# bikelights.net
KiCad netlist of a schematic drawn in EAGLE
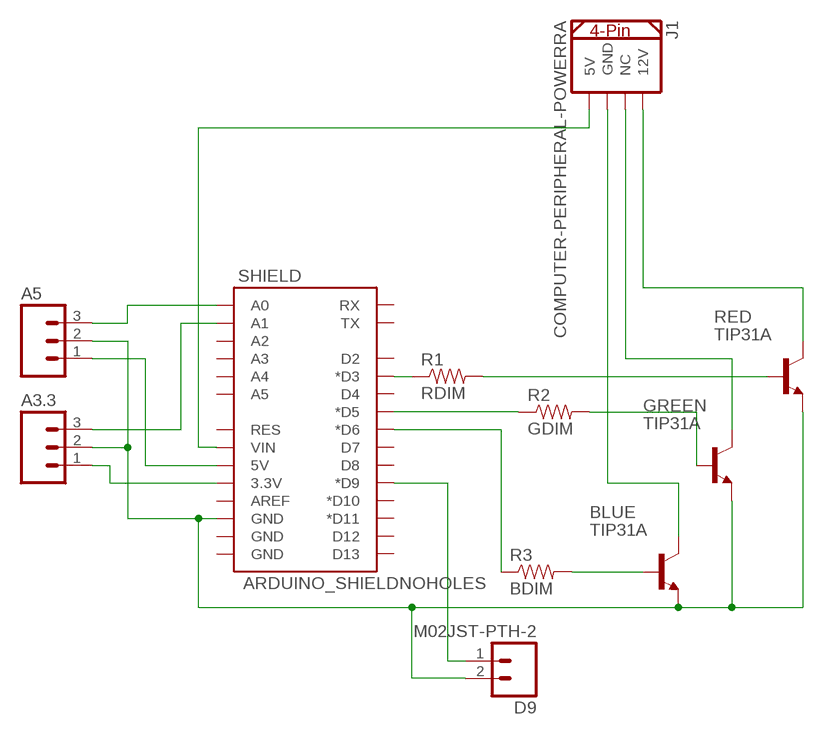
[diagram p0: schematic, sheet 1]

(export (version "E")
  (design (tool "Eeschema 10.0.6"))
  (components
    (comp (ref "A3.3")
      (value "M03JST-PTH")
      (footprint "eagle-import:JST-3-PTH")
      (libsource (lib "eagle-import") (part "M03JST-PTH"))
    )
    (comp (ref "A5")
      (value "M03JST-PTH")
      (footprint "eagle-import:JST-3-PTH")
      (libsource (lib "eagle-import") (part "M03JST-PTH"))
    )
    (comp (ref "BLUE")
      (value "TIP31A")
      (footprint "eagle-import:TO220")
      (libsource (lib "eagle-import") (part "TIP31A"))
    )
    (comp (ref "D9")
      (value "M02JST-PTH-2")
      (footprint "eagle-import:JST-2-PTH")
      (libsource (lib "eagle-import") (part "M02JST-PTH-2"))
    )
    (comp (ref "GREEN")
      (value "TIP31A")
      (footprint "eagle-import:TO220")
      (libsource (lib "eagle-import") (part "TIP31A"))
    )
    (comp (ref "J1")
      (value "COMPUTER-PERIPHERAL-POWERRA")
      (footprint "eagle-import:COMPUTER-PERIPHERAL-POWER-RA")
      (libsource (lib "eagle-import") (part "COMPUTER-PERIPHERAL-POWERRA"))
    )
    (comp (ref "R1")
      (value "RDIM")
      (footprint "eagle-import:AXIAL-0.3EZ")
      (libsource (lib "eagle-import") (part "RESISTOREZ"))
    )
    (comp (ref "R2")
      (value "GDIM")
      (footprint "eagle-import:AXIAL-0.3EZ")
      (libsource (lib "eagle-import") (part "RESISTOREZ"))
    )
    (comp (ref "R3")
      (value "BDIM")
      (footprint "eagle-import:AXIAL-0.3EZ")
      (libsource (lib "eagle-import") (part "RESISTOREZ"))
    )
    (comp (ref "RED")
      (value "TIP31A")
      (footprint "eagle-import:TO220")
      (libsource (lib "eagle-import") (part "TIP31A"))
    )
    (comp (ref "SHIELD")
      (value "ARDUINO_SHIELDNOHOLES")
      (footprint "eagle-import:DUEMILANOVE_SHIELD_NOHOLES")
      (libsource (lib "eagle-import") (part "ARDUINO_SHIELDNOHOLES"))
    )
  )
  (nets
    (net (code "1") (name "Net-(A3.3-Pad1)") (class "Default")
      (node (ref "A3.3") (pin "1") (pinfunction "1_1") (pintype "passive"))
      (node (ref "SHIELD") (pin "3.3V") (pinfunction "3.3V_3.3V") (pintype "bidirectional"))
    )
    (net (code "2") (name "Net-(A3.3-Pad3)") (class "Default")
      (node (ref "A3.3") (pin "3") (pinfunction "3_3") (pintype "passive"))
      (node (ref "SHIELD") (pin "A1") (pinfunction "A1_A1") (pintype "bidirectional"))
    )
    (net (code "3") (name "Net-(A5-Pad1)") (class "Default")
      (node (ref "A5") (pin "1") (pinfunction "1_1") (pintype "passive"))
      (node (ref "SHIELD") (pin "5V") (pinfunction "5V_5V") (pintype "bidirectional"))
    )
    (net (code "4") (name "Net-(A5-Pad3)") (class "Default")
      (node (ref "A5") (pin "3") (pinfunction "3_3") (pintype "passive"))
      (node (ref "SHIELD") (pin "A0") (pinfunction "A0_A0") (pintype "bidirectional"))
    )
    (net (code "5") (name "Net-(BLUE-B)") (class "Default")
      (node (ref "BLUE") (pin "1") (pinfunction "B_1") (pintype "passive"))
      (node (ref "R3") (pin "P$2") (pinfunction "2_P$2") (pintype "passive"))
    )
    (net (code "6") (name "Net-(BLUE-C)") (class "Default")
      (node (ref "BLUE") (pin "2") (pinfunction "C_2") (pintype "passive"))
      (node (ref "J1") (pin "GND") (pinfunction "GND_GND") (pintype "passive"))
    )
    (net (code "7") (name "Net-(BLUE-E)") (class "Default")
      (node (ref "A3.3") (pin "2") (pinfunction "2_2") (pintype "passive"))
      (node (ref "A5") (pin "2") (pinfunction "2_2") (pintype "passive"))
      (node (ref "BLUE") (pin "3") (pinfunction "E_3") (pintype "passive"))
      (node (ref "D9") (pin "2") (pinfunction "2_2") (pintype "passive"))
      (node (ref "GREEN") (pin "3") (pinfunction "E_3") (pintype "passive"))
      (node (ref "RED") (pin "3") (pinfunction "E_3") (pintype "passive"))
      (node (ref "SHIELD") (pin "GND@2") (pinfunction "GND_GND@2") (pintype "bidirectional"))
    )
    (net (code "8") (name "Net-(GREEN-B)") (class "Default")
      (node (ref "GREEN") (pin "1") (pinfunction "B_1") (pintype "passive"))
      (node (ref "R2") (pin "P$2") (pinfunction "2_P$2") (pintype "passive"))
    )
    (net (code "9") (name "Net-(GREEN-C)") (class "Default")
      (node (ref "GREEN") (pin "2") (pinfunction "C_2") (pintype "passive"))
      (node (ref "J1") (pin "NC") (pinfunction "NC_NC") (pintype "passive"))
    )
    (net (code "10") (name "Net-(J1-Pad5V)") (class "Default")
      (node (ref "J1") (pin "5V") (pinfunction "5V_5V") (pintype "passive"))
      (node (ref "SHIELD") (pin "VIN") (pinfunction "VIN_VIN") (pintype "bidirectional"))
    )
    (net (code "11") (name "Net-(R1-1)") (class "Default")
      (node (ref "R1") (pin "P$1") (pinfunction "1_P$1") (pintype "passive"))
      (node (ref "SHIELD") (pin "D3") (pinfunction "*D3_D3") (pintype "bidirectional"))
    )
    (net (code "12") (name "Net-(R1-2)") (class "Default")
      (node (ref "R1") (pin "P$2") (pinfunction "2_P$2") (pintype "passive"))
      (node (ref "RED") (pin "1") (pinfunction "B_1") (pintype "passive"))
    )
    (net (code "13") (name "Net-(R2-1)") (class "Default")
      (node (ref "R2") (pin "P$1") (pinfunction "1_P$1") (pintype "passive"))
      (node (ref "SHIELD") (pin "D5") (pinfunction "*D5_D5") (pintype "bidirectional"))
    )
    (net (code "14") (name "Net-(R3-1)") (class "Default")
      (node (ref "R3") (pin "P$1") (pinfunction "1_P$1") (pintype "passive"))
      (node (ref "SHIELD") (pin "D6") (pinfunction "*D6_D6") (pintype "bidirectional"))
    )
    (net (code "15") (name "Net-(RED-C)") (class "Default")
      (node (ref "J1") (pin "12V") (pinfunction "12V_12V") (pintype "passive"))
      (node (ref "RED") (pin "2") (pinfunction "C_2") (pintype "passive"))
    )
    (net (code "16") (name "Net-(SHIELD-*D9)") (class "Default")
      (node (ref "D9") (pin "1") (pinfunction "1_1") (pintype "passive"))
      (node (ref "SHIELD") (pin "D9") (pinfunction "*D9_D9") (pintype "bidirectional"))
    )
    (net (code "17") (name "unconnected-(SHIELD-*D10-PadD10)") (class "Default")
      (node (ref "SHIELD") (pin "D10") (pinfunction "*D10_D10") (pintype "bidirectional"))
    )
    (net (code "18") (name "unconnected-(SHIELD-*D11-PadD11)") (class "Default")
      (node (ref "SHIELD") (pin "D11") (pinfunction "*D11_D11") (pintype "bidirectional"))
    )
    (net (code "19") (name "unconnected-(SHIELD-GND-PadGND@0)") (class "Default")
      (node (ref "SHIELD") (pin "GND@0") (pinfunction "GND_GND@0") (pintype "bidirectional"))
    )
    (net (code "20") (name "unconnected-(SHIELD-GND-PadGND@1)") (class "Default")
      (node (ref "SHIELD") (pin "GND@1") (pinfunction "GND_GND@1") (pintype "bidirectional"))
    )
    (net (code "21") (name "unconnected-(SHIELD-PadA2)") (class "Default")
      (node (ref "SHIELD") (pin "A2") (pinfunction "A2_A2") (pintype "bidirectional"))
    )
    (net (code "22") (name "unconnected-(SHIELD-PadA3)") (class "Default")
      (node (ref "SHIELD") (pin "A3") (pinfunction "A3_A3") (pintype "bidirectional"))
    )
    (net (code "23") (name "unconnected-(SHIELD-PadA4)") (class "Default")
      (node (ref "SHIELD") (pin "A4") (pinfunction "A4_A4") (pintype "bidirectional"))
    )
    (net (code "24") (name "unconnected-(SHIELD-PadA5)") (class "Default")
      (node (ref "SHIELD") (pin "A5") (pinfunction "A5_A5") (pintype "bidirectional"))
    )
    (net (code "25") (name "unconnected-(SHIELD-PadAREF)") (class "Default")
      (node (ref "SHIELD") (pin "AREF") (pinfunction "AREF_AREF") (pintype "bidirectional"))
    )
    (net (code "26") (name "unconnected-(SHIELD-PadD2)") (class "Default")
      (node (ref "SHIELD") (pin "D2") (pinfunction "D2_D2") (pintype "bidirectional"))
    )
    (net (code "27") (name "unconnected-(SHIELD-PadD4)") (class "Default")
      (node (ref "SHIELD") (pin "D4") (pinfunction "D4_D4") (pintype "bidirectional"))
    )
    (net (code "28") (name "unconnected-(SHIELD-PadD7)") (class "Default")
      (node (ref "SHIELD") (pin "D7") (pinfunction "D7_D7") (pintype "bidirectional"))
    )
    (net (code "29") (name "unconnected-(SHIELD-PadD8)") (class "Default")
      (node (ref "SHIELD") (pin "D8") (pinfunction "D8_D8") (pintype "bidirectional"))
    )
    (net (code "30") (name "unconnected-(SHIELD-PadD12)") (class "Default")
      (node (ref "SHIELD") (pin "D12") (pinfunction "D12_D12") (pintype "bidirectional"))
    )
    (net (code "31") (name "unconnected-(SHIELD-PadD13)") (class "Default")
      (node (ref "SHIELD") (pin "D13") (pinfunction "D13_D13") (pintype "bidirectional"))
    )
    (net (code "32") (name "unconnected-(SHIELD-PadRES)") (class "Default")
      (node (ref "SHIELD") (pin "RES") (pinfunction "RES_RES") (pintype "bidirectional"))
    )
    (net (code "33") (name "unconnected-(SHIELD-PadRX)") (class "Default")
      (node (ref "SHIELD") (pin "RX") (pinfunction "RX_RX") (pintype "bidirectional"))
    )
    (net (code "34") (name "unconnected-(SHIELD-PadTX)") (class "Default")
      (node (ref "SHIELD") (pin "TX") (pinfunction "TX_TX") (pintype "bidirectional"))
    )
  )
)
